# FB.net
KiCad netlist of a schematic drawn in Altium Designer
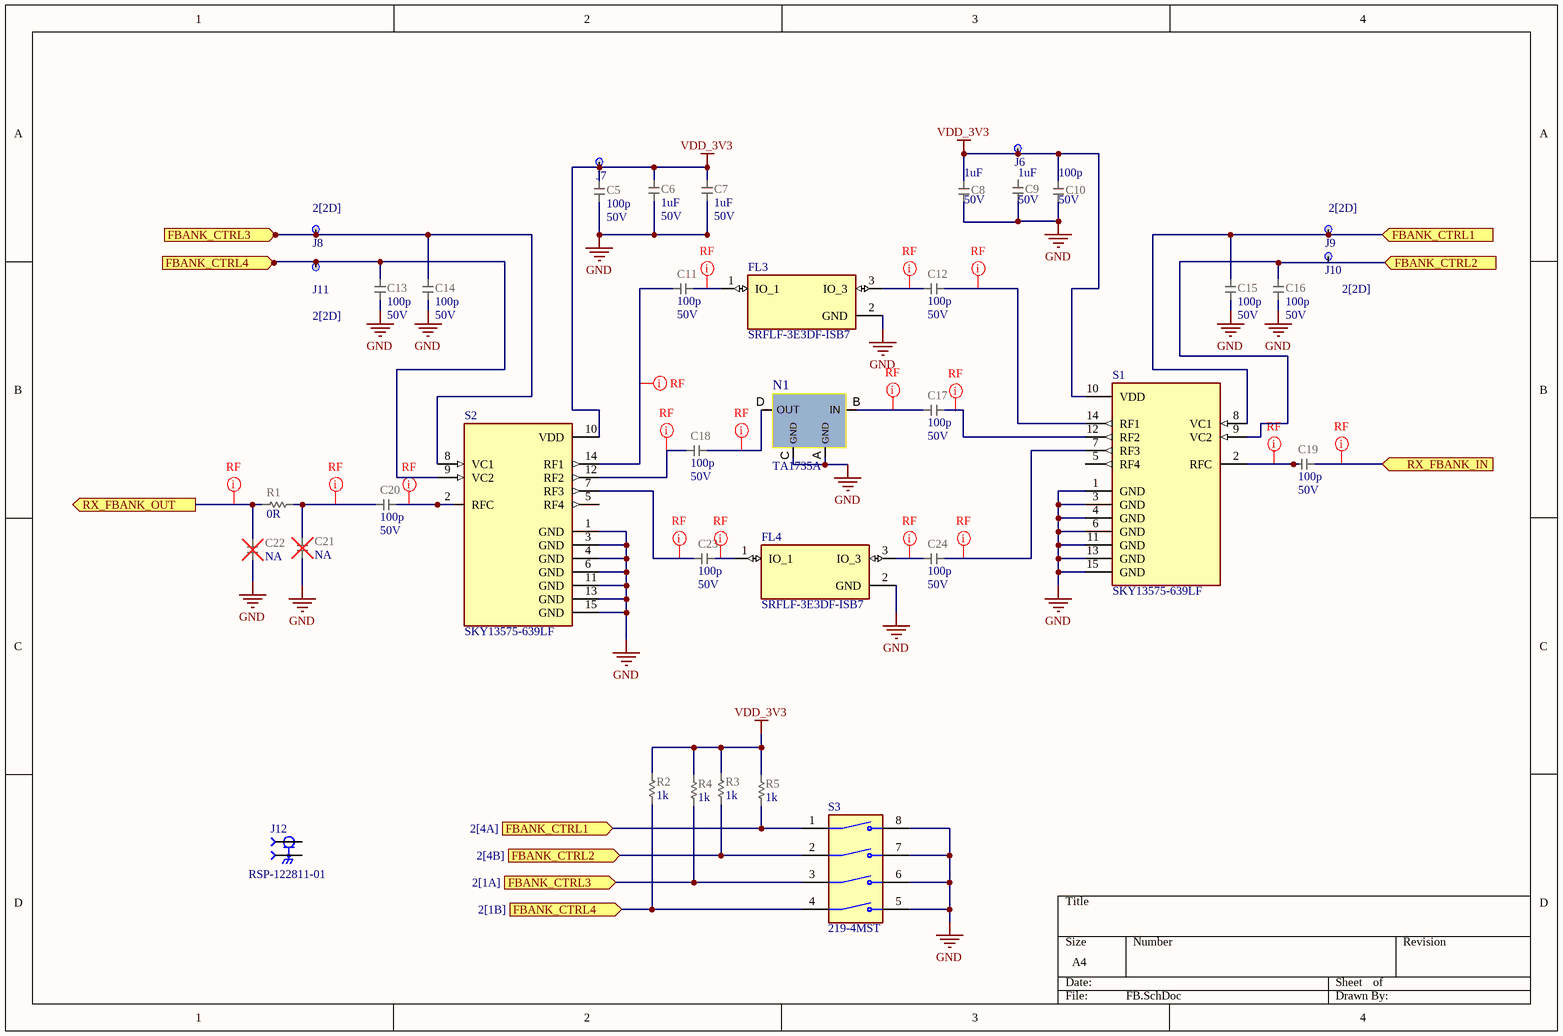
[diagram p0: FB.SchDoc]

(export (version "E")
  (design (tool "Eeschema 10.0.6"))
  (components
    (comp (ref "C5")
      (value "100p")
      (footprint "CAP_0603_UN1Q")
      (description "CAP")
      (fields
        (field (name "MANUFACTURER") "Murata")
        (field (name "PART NUMBER") "GCM188R71H102KA37J")
        (field (name "VOLTAGE") "50V")
      )
      (libsource (lib "robo_cam") (part "CMP-001-000378-11"))
    )
    (comp (ref "C6")
      (value "1uF")
      (footprint "CAP_0603_UN1Q")
      (description "CAP")
      (fields
        (field (name "PART NUMBER") "UMK107AB7105KA-T")
        (field (name "MANUFACTURER") "Taiyo Yuden")
        (field (name "VOLTAGE") "50V")
      )
      (libsource (lib "robo_cam") (part "CMP-001-000333-14"))
    )
    (comp (ref "C7")
      (value "1uF")
      (footprint "CAP_0603_UN1Q")
      (description "CAP")
      (fields
        (field (name "PART NUMBER") "UMK107AB7105KA-T")
        (field (name "MANUFACTURER") "Taiyo Yuden")
        (field (name "VOLTAGE") "50V")
      )
      (libsource (lib "robo_cam") (part "CMP-001-000333-14"))
    )
    (comp (ref "C8")
      (value "1uF")
      (footprint "CAP_0603_UN1Q")
      (description "CAP")
      (fields
        (field (name "PART NUMBER") "UMK107AB7105KA-T")
        (field (name "MANUFACTURER") "Taiyo Yuden")
        (field (name "VOLTAGE") "50V")
      )
      (libsource (lib "robo_cam") (part "CMP-001-000333-14"))
    )
    (comp (ref "C9")
      (value "1uF")
      (footprint "CAP_0603_UN1Q")
      (description "CAP")
      (fields
        (field (name "PART NUMBER") "UMK107AB7105KA-T")
        (field (name "MANUFACTURER") "Taiyo Yuden")
        (field (name "VOLTAGE") "50V")
      )
      (libsource (lib "robo_cam") (part "CMP-001-000333-14"))
    )
    (comp (ref "C10")
      (value "100p")
      (footprint "CAP_0603_UN1Q")
      (description "CAP")
      (fields
        (field (name "MANUFACTURER") "Murata")
        (field (name "PART NUMBER") "GCM188R71H102KA37J")
        (field (name "VOLTAGE") "50V")
      )
      (libsource (lib "robo_cam") (part "CMP-001-000378-11"))
    )
    (comp (ref "C11")
      (value "100p")
      (footprint "CAP_0603_UN1Q")
      (description "CAP")
      (fields
        (field (name "MANUFACTURER") "Murata")
        (field (name "PART NUMBER") "GCM188R71H102KA37J")
        (field (name "VOLTAGE") "50V")
      )
      (libsource (lib "robo_cam") (part "CMP-001-000378-11"))
    )
    (comp (ref "C12")
      (value "100p")
      (footprint "CAP_0603_UN1Q")
      (description "CAP")
      (fields
        (field (name "MANUFACTURER") "Murata")
        (field (name "PART NUMBER") "GCM188R71H102KA37J")
        (field (name "VOLTAGE") "50V")
      )
      (libsource (lib "robo_cam") (part "CMP-001-000378-11"))
    )
    (comp (ref "C13")
      (value "100p")
      (footprint "CAP_0603_UN1Q")
      (description "CAP")
      (fields
        (field (name "MANUFACTURER") "Murata")
        (field (name "PART NUMBER") "GCM188R71H102KA37J")
        (field (name "VOLTAGE") "50V")
      )
      (libsource (lib "robo_cam") (part "CMP-001-000378-11"))
    )
    (comp (ref "C14")
      (value "100p")
      (footprint "CAP_0603_UN1Q")
      (description "CAP")
      (fields
        (field (name "MANUFACTURER") "Murata")
        (field (name "PART NUMBER") "GCM188R71H102KA37J")
        (field (name "VOLTAGE") "50V")
      )
      (libsource (lib "robo_cam") (part "CMP-001-000378-11"))
    )
    (comp (ref "C15")
      (value "100p")
      (footprint "CAP_0603_UN1Q")
      (description "CAP")
      (fields
        (field (name "MANUFACTURER") "Murata")
        (field (name "PART NUMBER") "GCM188R71H102KA37J")
        (field (name "VOLTAGE") "50V")
      )
      (libsource (lib "robo_cam") (part "CMP-001-000378-11"))
    )
    (comp (ref "C16")
      (value "100p")
      (footprint "CAP_0603_UN1Q")
      (description "CAP")
      (fields
        (field (name "MANUFACTURER") "Murata")
        (field (name "PART NUMBER") "GCM188R71H102KA37J")
        (field (name "VOLTAGE") "50V")
      )
      (libsource (lib "robo_cam") (part "CMP-001-000378-11"))
    )
    (comp (ref "C17")
      (value "100p")
      (footprint "CAP_0603_UN1Q")
      (description "CAP")
      (fields
        (field (name "MANUFACTURER") "Murata")
        (field (name "PART NUMBER") "GCM188R71H102KA37J")
        (field (name "VOLTAGE") "50V")
      )
      (libsource (lib "robo_cam") (part "CMP-001-000378-11"))
    )
    (comp (ref "C18")
      (value "100p")
      (footprint "CAP_0603_UN1Q")
      (description "CAP")
      (fields
        (field (name "MANUFACTURER") "Murata")
        (field (name "PART NUMBER") "GCM188R71H102KA37J")
        (field (name "VOLTAGE") "50V")
      )
      (libsource (lib "robo_cam") (part "CMP-001-000378-11"))
    )
    (comp (ref "C19")
      (value "100p")
      (footprint "CAP_0603_UN1Q")
      (description "CAP")
      (fields
        (field (name "MANUFACTURER") "Murata")
        (field (name "PART NUMBER") "GCM188R71H102KA37J")
        (field (name "VOLTAGE") "50V")
      )
      (libsource (lib "robo_cam") (part "CMP-001-000378-11"))
    )
    (comp (ref "C20")
      (value "100p")
      (footprint "CAP_0603_UN1Q")
      (description "CAP")
      (fields
        (field (name "MANUFACTURER") "Murata")
        (field (name "PART NUMBER") "GCM188R71H102KA37J")
        (field (name "VOLTAGE") "50V")
      )
      (libsource (lib "robo_cam") (part "CMP-001-000378-11"))
    )
    (comp (ref "C21")
      (value "NA")
      (footprint "CAP_0603_UN1Q")
      (description "Not Assembled - CAP")
      (fields (field (name "Comment") "CAP_0603_NA"))
      (libsource (lib "robo_cam") (part "CMP-001-000259-10"))
    )
    (comp (ref "C22")
      (value "NA")
      (footprint "CAP_0603_UN1Q")
      (description "Not Assembled - CAP")
      (fields (field (name "Comment") "CAP_0603_NA"))
      (libsource (lib "robo_cam") (part "CMP-001-000259-10"))
    )
    (comp (ref "C23")
      (value "100p")
      (footprint "CAP_0603_UN1Q")
      (description "CAP")
      (fields
        (field (name "MANUFACTURER") "Murata")
        (field (name "PART NUMBER") "GCM188R71H102KA37J")
        (field (name "VOLTAGE") "50V")
      )
      (libsource (lib "robo_cam") (part "CMP-001-000378-11"))
    )
    (comp (ref "C24")
      (value "100p")
      (footprint "CAP_0603_UN1Q")
      (description "CAP")
      (fields
        (field (name "MANUFACTURER") "Murata")
        (field (name "PART NUMBER") "GCM188R71H102KA37J")
        (field (name "VOLTAGE") "50V")
      )
      (libsource (lib "robo_cam") (part "CMP-001-000378-11"))
    )
    (comp (ref "FL3")
      (value "SRFLF-3E3DF-ISB7")
      (footprint "FIL_SRFLF-3E3DF-ISB7")
      (description "3.4mm x 3.3mm SMD ISM 915MHz Low Pass Filter")
      (fields (field (name "MF") "Suntsu Electronics, Inc"))
      (libsource (lib "SRFLF-3E3DF-ISB7") (part "SRFLF-3E3DF-ISB7"))
    )
    (comp (ref "FL4")
      (value "SRFLF-3E3DF-ISB7")
      (footprint "FIL_SRFLF-3E3DF-ISB7")
      (description "3.4mm x 3.3mm SMD ISM 915MHz Low Pass Filter")
      (fields (field (name "MF") "Suntsu Electronics, Inc"))
      (libsource (lib "SRFLF-3E3DF-ISB7") (part "SRFLF-3E3DF-ISB7"))
    )
    (comp (ref "J6")
      (value "Testpoint, Surface, 1.0mm")
      (footprint "TP_1mm_UN1Q")
      (description "Testpoint 1.0mm")
      (fields (field (name "PART NUMBER") "TP 1mm"))
      (libsource (lib "robo_cam") (part "CMP-001-000153-12"))
    )
    (comp (ref "J7")
      (value "Testpoint, Surface, 1.0mm")
      (footprint "TP_1mm_UN1Q")
      (description "Testpoint 1.0mm")
      (fields (field (name "PART NUMBER") "TP 1mm"))
      (libsource (lib "robo_cam") (part "CMP-001-000153-12"))
    )
    (comp (ref "J8")
      (value "Testpoint, Surface, 1.0mm")
      (footprint "TP_1mm_UN1Q")
      (description "Testpoint 1.0mm")
      (fields (field (name "PART NUMBER") "TP 1mm"))
      (libsource (lib "robo_cam") (part "CMP-001-000153-12"))
    )
    (comp (ref "J9")
      (value "Testpoint, Surface, 1.0mm")
      (footprint "TP_1mm_UN1Q")
      (description "Testpoint 1.0mm")
      (fields (field (name "PART NUMBER") "TP 1mm"))
      (libsource (lib "robo_cam") (part "CMP-001-000153-12"))
    )
    (comp (ref "J10")
      (value "Testpoint, Surface, 1.0mm")
      (footprint "TP_1mm_UN1Q")
      (description "Testpoint 1.0mm")
      (fields (field (name "PART NUMBER") "TP 1mm"))
      (libsource (lib "robo_cam") (part "CMP-001-000153-12"))
    )
    (comp (ref "J11")
      (value "Testpoint, Surface, 1.0mm")
      (footprint "TP_1mm_UN1Q")
      (description "Testpoint 1.0mm")
      (fields (field (name "PART NUMBER") "TP 1mm"))
      (libsource (lib "robo_cam") (part "CMP-001-000153-12"))
    )
    (comp (ref "J12")
      (value "RSP-122811-01")
      (footprint "SAMTEC_RSP-122811-01")
      (fields (field (name "MF") "{'manufacturer': u'Samtec Inc.'}"))
      (libsource (lib "RSP-122811-01") (part "RSP-122811-01"))
    )
    (comp (ref "N1")
      (value "TA1735A")
      (footprint "TA1735A_SM2016-4")
      (description "867.5 MHz SAW Filter, IL 3.5 dB, 15 MHz BW")
      (fields
        (field (name "PART NUMBER") "TA1735A")
        (field (name "MANUFACTURER") "TAI-SAW")
        (field (name "MANUFACTURER_1") "TST - Tamsan")
      )
      (libsource (lib "robo_cam") (part "CMP-001-001528-1"))
    )
    (comp (ref "R1")
      (value "0R")
      (footprint "RES_0603_UN1Q")
      (description "RES")
      (fields (field (name "MANUFACTURER") "YAGEO") (field (name "TOLERANCE") "5%"))
      (libsource (lib "robo_cam") (part "CMP-001-000441-13"))
    )
    (comp (ref "R2")
      (value "1k")
      (footprint "RES_0603_UN1Q")
      (description "RES")
      (fields (field (name "MANUFACTURER") "YAGEO") (field (name "TOLERANCE") "5%"))
      (libsource (lib "robo_cam") (part "CMP-001-000441-13"))
    )
    (comp (ref "R3")
      (value "1k")
      (footprint "RES_0603_UN1Q")
      (description "RES")
      (fields (field (name "MANUFACTURER") "YAGEO") (field (name "TOLERANCE") "5%"))
      (libsource (lib "robo_cam") (part "CMP-001-000441-13"))
    )
    (comp (ref "R4")
      (value "1k")
      (footprint "RES_0603_UN1Q")
      (description "RES")
      (fields (field (name "MANUFACTURER") "YAGEO") (field (name "TOLERANCE") "5%"))
      (libsource (lib "robo_cam") (part "CMP-001-000441-13"))
    )
    (comp (ref "R5")
      (value "1k")
      (footprint "RES_0603_UN1Q")
      (description "RES")
      (fields (field (name "MANUFACTURER") "YAGEO") (field (name "TOLERANCE") "5%"))
      (libsource (lib "robo_cam") (part "CMP-001-000441-13"))
    )
    (comp (ref "S1")
      (value "SKY13575-639LF")
      (footprint "SW_SKY13575-639LF")
      (description "RF Switch IC 802.11a/b/g/n/ac SP4T 6 GHz 50Ohm 14-QFN (1.6x1.6)")
      (fields (field (name "MF") "Skyworks Solutions"))
      (libsource (lib "SKY13575-639LF") (part "SKY13575-639LF"))
    )
    (comp (ref "S2")
      (value "SKY13575-639LF")
      (footprint "SW_SKY13575-639LF")
      (description "RF Switch IC 802.11a/b/g/n/ac SP4T 6 GHz 50Ohm 14-QFN (1.6x1.6)")
      (fields (field (name "MF") "Skyworks Solutions"))
      (libsource (lib "") (part "SKY13575-639LF_1"))
    )
    (comp (ref "S3")
      (value "219-4MST")
      (footprint "SW_219-4MST")
      (description "Dip Switch SPST 4 Position Surface Mount Slide (Standard) Actuator 100mA 20VDC")
      (fields (field (name "MF") "CTS Electronic Components"))
      (libsource (lib "altium-import") (part "root_0_219-4MST_"))
    )
  )
  (nets
    (net (code "1") (name "/FBANK_CTRL1") (class "Default")
      (node (ref "C15") (pin "1") (pinfunction "1_1") (pintype "passive"))
      (node (ref "J9") (pin "1") (pinfunction "TP_1") (pintype "passive"))
      (node (ref "R5") (pin "1") (pinfunction "1_1") (pintype "passive"))
      (node (ref "S1") (pin "8") (pinfunction "VC1_8") (pintype "input"))
      (node (ref "S3") (pin "1") (pinfunction "1_1") (pintype "passive"))
    )
    (net (code "2") (name "/FBANK_CTRL2") (class "Default")
      (node (ref "C16") (pin "1") (pinfunction "1_1") (pintype "passive"))
      (node (ref "R3") (pin "1") (pinfunction "1_1") (pintype "passive"))
      (node (ref "S1") (pin "9") (pinfunction "VC2_9") (pintype "input"))
      (node (ref "S3") (pin "2") (pinfunction "2_2") (pintype "passive"))
    )
    (net (code "3") (name "/FBANK_CTRL3") (class "Default")
      (node (ref "C14") (pin "1") (pinfunction "1_1") (pintype "passive"))
      (node (ref "J8") (pin "1") (pinfunction "TP_1") (pintype "passive"))
      (node (ref "R4") (pin "1") (pinfunction "1_1") (pintype "passive"))
      (node (ref "S2") (pin "8") (pinfunction "VC1_8") (pintype "input"))
      (node (ref "S3") (pin "3") (pinfunction "3_3") (pintype "passive"))
    )
    (net (code "4") (name "/FBANK_CTRL4") (class "Default")
      (node (ref "C13") (pin "1") (pinfunction "1_1") (pintype "passive"))
      (node (ref "J11") (pin "1") (pinfunction "TP_1") (pintype "passive"))
      (node (ref "R2") (pin "1") (pinfunction "1_1") (pintype "passive"))
      (node (ref "S2") (pin "9") (pinfunction "VC2_9") (pintype "input"))
      (node (ref "S3") (pin "4") (pinfunction "4_4") (pintype "passive"))
    )
    (net (code "5") (name "/RX_FBANK_IN") (class "Default")
      (node (ref "C19") (pin "1") (pinfunction "1_1") (pintype "passive"))
    )
    (net (code "6") (name "/RX_FBANK_OUT") (class "Default")
      (node (ref "C22") (pin "2") (pinfunction "2_2") (pintype "passive"))
      (node (ref "R1") (pin "1") (pinfunction "1_1") (pintype "passive"))
    )
    (net (code "7") (name "GND") (class "Default")
      (node (ref "C10") (pin "2") (pinfunction "2_2") (pintype "passive"))
      (node (ref "C13") (pin "2") (pinfunction "2_2") (pintype "passive"))
      (node (ref "C14") (pin "2") (pinfunction "2_2") (pintype "passive"))
      (node (ref "C15") (pin "2") (pinfunction "2_2") (pintype "passive"))
      (node (ref "C16") (pin "2") (pinfunction "2_2") (pintype "passive"))
      (node (ref "C21") (pin "1") (pinfunction "1_1") (pintype "passive"))
      (node (ref "C22") (pin "1") (pinfunction "1_1") (pintype "passive"))
      (node (ref "C5") (pin "2") (pinfunction "2_2") (pintype "passive"))
      (node (ref "C6") (pin "1") (pinfunction "1_1") (pintype "passive"))
      (node (ref "C7") (pin "1") (pinfunction "1_1") (pintype "passive"))
      (node (ref "C8") (pin "1") (pinfunction "1_1") (pintype "passive"))
      (node (ref "C9") (pin "1") (pinfunction "1_1") (pintype "passive"))
      (node (ref "FL3") (pin "2") (pinfunction "GND_2") (pintype "power_in"))
      (node (ref "FL4") (pin "2") (pinfunction "GND_2") (pintype "power_in"))
      (node (ref "N1") (pin "A") (pinfunction "GND_A") (pintype "passive"))
      (node (ref "N1") (pin "C") (pinfunction "GND_C") (pintype "passive"))
      (node (ref "S1") (pin "1") (pinfunction "GND_1") (pintype "power_in"))
      (node (ref "S1") (pin "11") (pinfunction "GND_11") (pintype "power_in"))
      (node (ref "S1") (pin "13") (pinfunction "GND_13") (pintype "power_in"))
      (node (ref "S1") (pin "15") (pinfunction "GND_15") (pintype "power_in"))
      (node (ref "S1") (pin "3") (pinfunction "GND_3") (pintype "power_in"))
      (node (ref "S1") (pin "4") (pinfunction "GND_4") (pintype "power_in"))
      (node (ref "S1") (pin "6") (pinfunction "GND_6") (pintype "power_in"))
      (node (ref "S2") (pin "1") (pinfunction "GND_1") (pintype "power_in"))
      (node (ref "S2") (pin "11") (pinfunction "GND_11") (pintype "power_in"))
      (node (ref "S2") (pin "13") (pinfunction "GND_13") (pintype "power_in"))
      (node (ref "S2") (pin "15") (pinfunction "GND_15") (pintype "power_in"))
      (node (ref "S2") (pin "3") (pinfunction "GND_3") (pintype "power_in"))
      (node (ref "S2") (pin "4") (pinfunction "GND_4") (pintype "power_in"))
      (node (ref "S2") (pin "6") (pinfunction "GND_6") (pintype "power_in"))
      (node (ref "S3") (pin "5") (pinfunction "5_5") (pintype "passive"))
      (node (ref "S3") (pin "6") (pinfunction "6_6") (pintype "passive"))
      (node (ref "S3") (pin "7") (pinfunction "7_7") (pintype "passive"))
      (node (ref "S3") (pin "8") (pinfunction "8_8") (pintype "passive"))
    )
    (net (code "8") (name "Net-(C20-Pad2)") (class "Default")
      (node (ref "C20") (pin "2") (pinfunction "2_2") (pintype "passive"))
      (node (ref "C21") (pin "2") (pinfunction "2_2") (pintype "passive"))
      (node (ref "R1") (pin "2") (pinfunction "2_2") (pintype "passive"))
    )
    (net (code "9") (name "Net-(FL3-IO_1)") (class "Default")
      (node (ref "C11") (pin "1") (pinfunction "1_1") (pintype "passive"))
      (node (ref "FL3") (pin "1") (pinfunction "IO_1_1") (pintype "bidirectional"))
    )
    (net (code "10") (name "Net-(FL3-IO_3)") (class "Default")
      (node (ref "C12") (pin "2") (pinfunction "2_2") (pintype "passive"))
      (node (ref "FL3") (pin "3") (pinfunction "IO_3_3") (pintype "bidirectional"))
    )
    (net (code "11") (name "Net-(FL4-IO_1)") (class "Default")
      (node (ref "C23") (pin "1") (pinfunction "1_1") (pintype "passive"))
      (node (ref "FL4") (pin "1") (pinfunction "IO_1_1") (pintype "bidirectional"))
    )
    (net (code "12") (name "Net-(FL4-IO_3)") (class "Default")
      (node (ref "C24") (pin "2") (pinfunction "2_2") (pintype "passive"))
      (node (ref "FL4") (pin "3") (pinfunction "IO_3_3") (pintype "bidirectional"))
    )
    (net (code "13") (name "Net-(J12-GND-PadG1)") (class "Default")
      (node (ref "J12") (pin "G1") (pinfunction "GND_G1") (pintype "passive"))
      (node (ref "J12") (pin "G2") (pinfunction "GND_G2") (pintype "passive"))
    )
    (net (code "14") (name "Net-(N1-IN)") (class "Default")
      (node (ref "C17") (pin "2") (pinfunction "2_2") (pintype "passive"))
      (node (ref "N1") (pin "B") (pinfunction "IN_B") (pintype "passive"))
    )
    (net (code "15") (name "Net-(N1-OUT)") (class "Default")
      (node (ref "C18") (pin "1") (pinfunction "1_1") (pintype "passive"))
      (node (ref "N1") (pin "D") (pinfunction "OUT_D") (pintype "passive"))
    )
    (net (code "16") (name "Net-(S1-RF1)") (class "Default")
      (node (ref "C12") (pin "1") (pinfunction "1_1") (pintype "passive"))
      (node (ref "S1") (pin "14") (pinfunction "RF1_14") (pintype "output"))
    )
    (net (code "17") (name "Net-(S1-RF2)") (class "Default")
      (node (ref "C17") (pin "1") (pinfunction "1_1") (pintype "passive"))
      (node (ref "S1") (pin "12") (pinfunction "RF2_12") (pintype "output"))
    )
    (net (code "18") (name "Net-(S1-RF3)") (class "Default")
      (node (ref "C24") (pin "1") (pinfunction "1_1") (pintype "passive"))
      (node (ref "S1") (pin "7") (pinfunction "RF3_7") (pintype "output"))
    )
    (net (code "19") (name "Net-(S1-RFC)") (class "Default")
      (node (ref "C19") (pin "2") (pinfunction "2_2") (pintype "passive"))
      (node (ref "S1") (pin "2") (pinfunction "RFC_2") (pintype "passive"))
    )
    (net (code "20") (name "Net-(S2-RF1)") (class "Default")
      (node (ref "C11") (pin "2") (pinfunction "2_2") (pintype "passive"))
      (node (ref "S2") (pin "14") (pinfunction "RF1_14") (pintype "output"))
    )
    (net (code "21") (name "Net-(S2-RF2)") (class "Default")
      (node (ref "C18") (pin "2") (pinfunction "2_2") (pintype "passive"))
      (node (ref "S2") (pin "12") (pinfunction "RF2_12") (pintype "output"))
    )
    (net (code "22") (name "Net-(S2-RF3)") (class "Default")
      (node (ref "C23") (pin "2") (pinfunction "2_2") (pintype "passive"))
      (node (ref "S2") (pin "7") (pinfunction "RF3_7") (pintype "output"))
    )
    (net (code "23") (name "Net-(S2-RFC)") (class "Default")
      (node (ref "C20") (pin "1") (pinfunction "1_1") (pintype "passive"))
      (node (ref "S2") (pin "2") (pinfunction "RFC_2") (pintype "passive"))
    )
    (net (code "24") (name "VDD_3V3") (class "Default")
      (node (ref "C10") (pin "1") (pinfunction "1_1") (pintype "passive"))
      (node (ref "C5") (pin "1") (pinfunction "1_1") (pintype "passive"))
      (node (ref "C6") (pin "2") (pinfunction "2_2") (pintype "passive"))
      (node (ref "C7") (pin "2") (pinfunction "2_2") (pintype "passive"))
      (node (ref "C8") (pin "2") (pinfunction "2_2") (pintype "passive"))
      (node (ref "J6") (pin "1") (pinfunction "TP_1") (pintype "passive"))
      (node (ref "J7") (pin "1") (pinfunction "TP_1") (pintype "passive"))
      (node (ref "R2") (pin "2") (pinfunction "2_2") (pintype "passive"))
      (node (ref "R3") (pin "2") (pinfunction "2_2") (pintype "passive"))
      (node (ref "R4") (pin "2") (pinfunction "2_2") (pintype "passive"))
      (node (ref "R5") (pin "2") (pinfunction "2_2") (pintype "passive"))
      (node (ref "S1") (pin "10") (pinfunction "VDD_10") (pintype "power_in"))
      (node (ref "S2") (pin "10") (pinfunction "VDD_10") (pintype "power_in"))
    )
    (net (code "25") (name "unconnected-(C9-Pad2)") (class "Default")
      (node (ref "C9") (pin "2") (pinfunction "2_2") (pintype "passive"))
    )
    (net (code "26") (name "unconnected-(J10-TP-Pad1)") (class "Default")
      (node (ref "J10") (pin "1") (pinfunction "TP_1") (pintype "passive"))
    )
    (net (code "27") (name "unconnected-(J12-Pad1)") (class "Default")
      (node (ref "J12") (pin "1") (pinfunction "1_1") (pintype "passive"))
    )
    (net (code "28") (name "unconnected-(S1-RF4-Pad5)") (class "Default")
      (node (ref "S1") (pin "5") (pinfunction "RF4_5") (pintype "output"))
    )
    (net (code "29") (name "unconnected-(S2-RF4-Pad5)") (class "Default")
      (node (ref "S2") (pin "5") (pinfunction "RF4_5") (pintype "output"))
    )
  )
)
